# comparator_mezzanine.net
KiCad netlist of a schematic drawn in Altium Designer
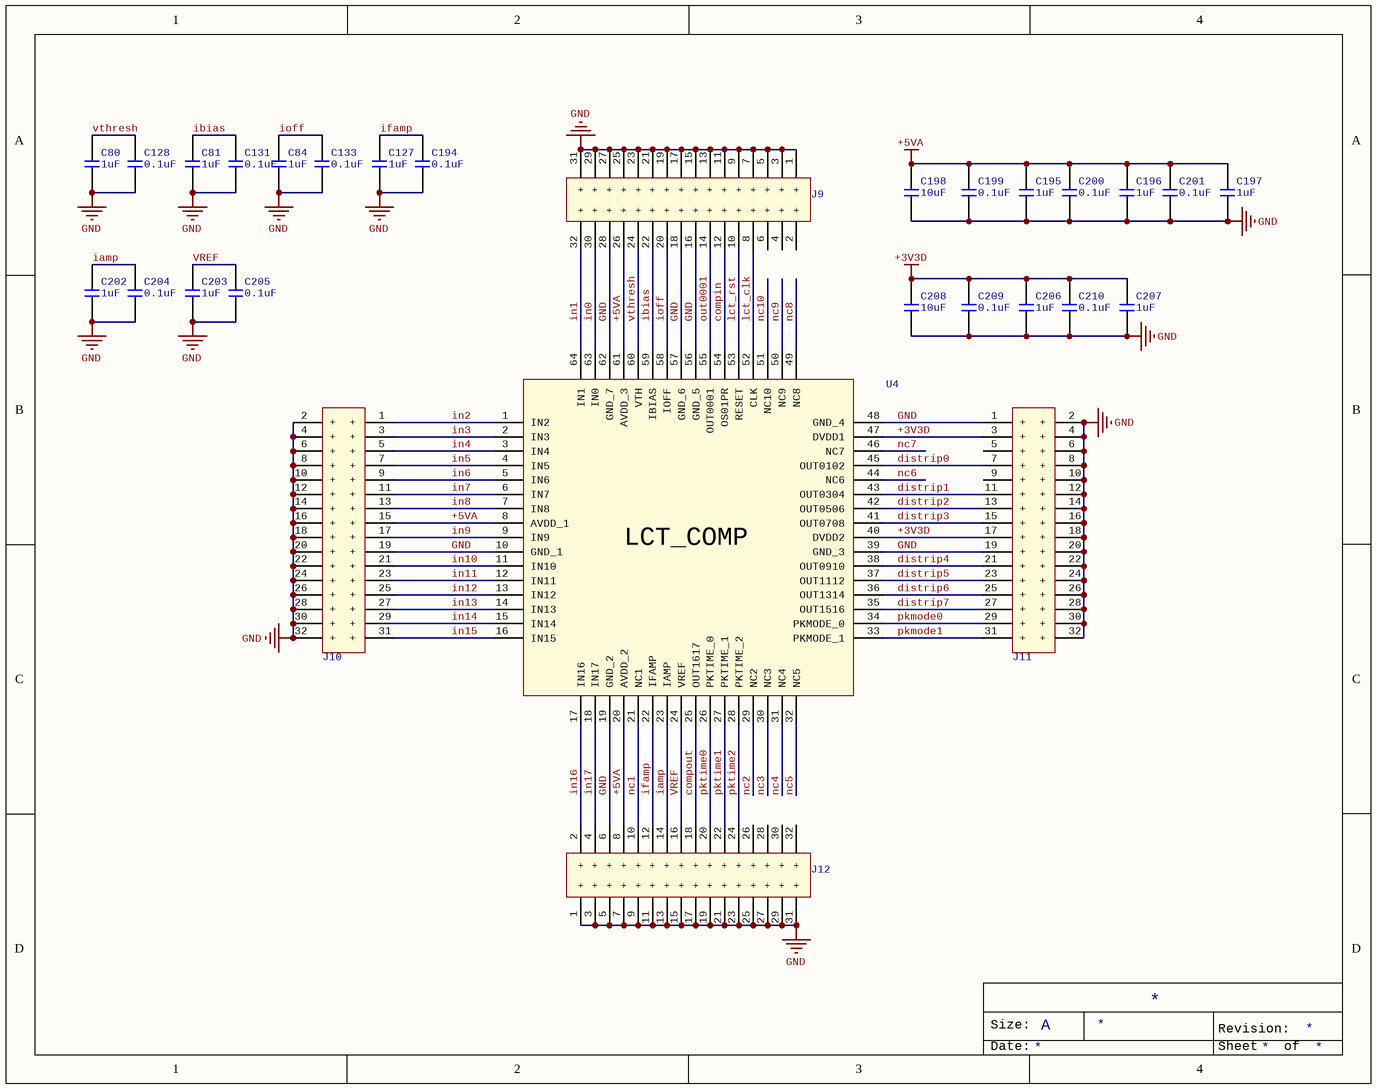
[diagram p0: comparator_mezzanine.SchDoc]

(export (version "E")
  (design (tool "Eeschema 10.0.6"))
  (components
    (comp (ref "C80")
      (value "1uF")
      (footprint "C0603")
      (description "CAP2, CER, 1.0uF, 10%, 25V, 0603")
      (libsource (lib "stdlib") (part "Murata/GRM188R61E105KA12D"))
    )
    (comp (ref "C81")
      (value "1uF")
      (footprint "C0603")
      (description "CAP2, CER, 1.0uF, 10%, 25V, 0603")
      (libsource (lib "stdlib") (part "Murata/GRM188R61E105KA12D"))
    )
    (comp (ref "C84")
      (value "1uF")
      (footprint "C0603")
      (description "CAP2, CER, 1.0uF, 10%, 25V, 0603")
      (libsource (lib "stdlib") (part "Murata/GRM188R61E105KA12D"))
    )
    (comp (ref "C127")
      (value "1uF")
      (footprint "C0603")
      (description "CAP2, CER, 1.0uF, 10%, 25V, 0603")
      (libsource (lib "stdlib") (part "Murata/GRM188R61E105KA12D"))
    )
    (comp (ref "C128")
      (value "0.1uF")
      (footprint "C0603")
      (description "CAP-CER, 2, 0.1uF, 10%, 50V, 0603, X7R")
      (fields
        (field (name "MANUFACTURER") "AVX Corporation")
        (field (name "MANUFACTURER PART NUMBER") "06035C104KAT2A")
      )
      (libsource (lib "stdlib") (part "CAP/06035C104KAT2A"))
    )
    (comp (ref "C131")
      (value "0.1uF")
      (footprint "C0603")
      (description "CAP-CER, 2, 0.1uF, 10%, 50V, 0603, X7R")
      (fields
        (field (name "MANUFACTURER") "AVX Corporation")
        (field (name "MANUFACTURER PART NUMBER") "06035C104KAT2A")
      )
      (libsource (lib "stdlib") (part "CAP/06035C104KAT2A"))
    )
    (comp (ref "C133")
      (value "0.1uF")
      (footprint "C0603")
      (description "CAP-CER, 2, 0.1uF, 10%, 50V, 0603, X7R")
      (fields
        (field (name "MANUFACTURER") "AVX Corporation")
        (field (name "MANUFACTURER PART NUMBER") "06035C104KAT2A")
      )
      (libsource (lib "stdlib") (part "CAP/06035C104KAT2A"))
    )
    (comp (ref "C194")
      (value "0.1uF")
      (footprint "C0603")
      (description "CAP-CER, 2, 0.1uF, 10%, 50V, 0603, X7R")
      (fields
        (field (name "MANUFACTURER") "AVX Corporation")
        (field (name "MANUFACTURER PART NUMBER") "06035C104KAT2A")
      )
      (libsource (lib "stdlib") (part "CAP/06035C104KAT2A"))
    )
    (comp (ref "C195")
      (value "1uF")
      (footprint "C0603")
      (description "CAP2, CER, 1.0uF, 10%, 25V, 0603")
      (libsource (lib "stdlib") (part "Murata/GRM188R61E105KA12D"))
    )
    (comp (ref "C196")
      (value "1uF")
      (footprint "C0603")
      (description "CAP2, CER, 1.0uF, 10%, 25V, 0603")
      (libsource (lib "stdlib") (part "Murata/GRM188R61E105KA12D"))
    )
    (comp (ref "C197")
      (value "1uF")
      (footprint "C0603")
      (description "CAP2, CER, 1.0uF, 10%, 25V, 0603")
      (libsource (lib "stdlib") (part "Murata/GRM188R61E105KA12D"))
    )
    (comp (ref "C198")
      (value "10uF")
      (footprint "c1206")
      (description "CAP-CER, 2, 10uF, 10%, 35V, 1206")
      (fields
        (field (name "MANUFACTURER") "Taiyo Yuden")
        (field (name "MANUFACTURER PART NUMBER") "GMK316F106ZL-T")
      )
      (libsource (lib "stdlib") (part "CAP/GMK316F106ZL-T"))
    )
    (comp (ref "C199")
      (value "0.1uF")
      (footprint "C0603")
      (description "CAP-CER, 2, 0.1uF, 10%, 50V, 0603, X7R")
      (fields
        (field (name "MANUFACTURER") "AVX Corporation")
        (field (name "MANUFACTURER PART NUMBER") "06035C104KAT2A")
      )
      (libsource (lib "stdlib") (part "CAP/06035C104KAT2A"))
    )
    (comp (ref "C200")
      (value "0.1uF")
      (footprint "C0603")
      (description "CAP-CER, 2, 0.1uF, 10%, 50V, 0603, X7R")
      (fields
        (field (name "MANUFACTURER") "AVX Corporation")
        (field (name "MANUFACTURER PART NUMBER") "06035C104KAT2A")
      )
      (libsource (lib "stdlib") (part "CAP/06035C104KAT2A"))
    )
    (comp (ref "C201")
      (value "0.1uF")
      (footprint "C0603")
      (description "CAP-CER, 2, 0.1uF, 10%, 50V, 0603, X7R")
      (fields
        (field (name "MANUFACTURER") "AVX Corporation")
        (field (name "MANUFACTURER PART NUMBER") "06035C104KAT2A")
      )
      (libsource (lib "stdlib") (part "CAP/06035C104KAT2A"))
    )
    (comp (ref "C202")
      (value "1uF")
      (footprint "C0603")
      (description "CAP2, CER, 1.0uF, 10%, 25V, 0603")
      (libsource (lib "stdlib") (part "Murata/GRM188R61E105KA12D"))
    )
    (comp (ref "C203")
      (value "1uF")
      (footprint "C0603")
      (description "CAP2, CER, 1.0uF, 10%, 25V, 0603")
      (libsource (lib "stdlib") (part "Murata/GRM188R61E105KA12D"))
    )
    (comp (ref "C204")
      (value "0.1uF")
      (footprint "C0603")
      (description "CAP-CER, 2, 0.1uF, 10%, 50V, 0603, X7R")
      (fields
        (field (name "MANUFACTURER") "AVX Corporation")
        (field (name "MANUFACTURER PART NUMBER") "06035C104KAT2A")
      )
      (libsource (lib "stdlib") (part "CAP/06035C104KAT2A"))
    )
    (comp (ref "C205")
      (value "0.1uF")
      (footprint "C0603")
      (description "CAP-CER, 2, 0.1uF, 10%, 50V, 0603, X7R")
      (fields
        (field (name "MANUFACTURER") "AVX Corporation")
        (field (name "MANUFACTURER PART NUMBER") "06035C104KAT2A")
      )
      (libsource (lib "stdlib") (part "CAP/06035C104KAT2A"))
    )
    (comp (ref "C206")
      (value "1uF")
      (footprint "C0603")
      (description "CAP2, CER, 1.0uF, 10%, 25V, 0603")
      (libsource (lib "stdlib") (part "Murata/GRM188R61E105KA12D"))
    )
    (comp (ref "C207")
      (value "1uF")
      (footprint "C0603")
      (description "CAP2, CER, 1.0uF, 10%, 25V, 0603")
      (libsource (lib "stdlib") (part "Murata/GRM188R61E105KA12D"))
    )
    (comp (ref "C208")
      (value "10uF")
      (footprint "c1206")
      (description "CAP-CER, 2, 10uF, 10%, 35V, 1206")
      (fields
        (field (name "MANUFACTURER") "Taiyo Yuden")
        (field (name "MANUFACTURER PART NUMBER") "GMK316F106ZL-T")
      )
      (libsource (lib "stdlib") (part "CAP/GMK316F106ZL-T"))
    )
    (comp (ref "C209")
      (value "0.1uF")
      (footprint "C0603")
      (description "CAP-CER, 2, 0.1uF, 10%, 50V, 0603, X7R")
      (fields
        (field (name "MANUFACTURER") "AVX Corporation")
        (field (name "MANUFACTURER PART NUMBER") "06035C104KAT2A")
      )
      (libsource (lib "stdlib") (part "CAP/06035C104KAT2A"))
    )
    (comp (ref "C210")
      (value "0.1uF")
      (footprint "C0603")
      (description "CAP-CER, 2, 0.1uF, 10%, 50V, 0603, X7R")
      (fields
        (field (name "MANUFACTURER") "AVX Corporation")
        (field (name "MANUFACTURER PART NUMBER") "06035C104KAT2A")
      )
      (libsource (lib "stdlib") (part "CAP/06035C104KAT2A"))
    )
    (comp (ref "J9")
      (value "HEADER 16x02")
      (footprint "HEADER 16X02")
      (libsource (lib "stdlib") (part "HEADER 16x02"))
    )
    (comp (ref "J10")
      (value "HEADER 16x02")
      (footprint "HEADER 16X02")
      (libsource (lib "stdlib") (part "HEADER 16x02"))
    )
    (comp (ref "J11")
      (value "HEADER 16x02")
      (footprint "HEADER 16X02")
      (libsource (lib "") (part "HEADER 16x02_1"))
    )
    (comp (ref "J12")
      (value "HEADER 16x02")
      (footprint "HEADER 16X02")
      (libsource (lib "") (part "HEADER 16x02_2"))
    )
    (comp (ref "U4")
      (value "UCLA/LCT_COMP")
      (footprint "FPQ-64-0.8-10")
      (description "UCLA LCT Comparator")
      (libsource (lib "stdlib") (part "UCLA/LCT_COMP"))
    )
  )
  (nets
    (net (code "1") (name "+3V3D") (class "Default")
      (node (ref "C206") (pin "2") (pinfunction "2_2") (pintype "passive"))
      (node (ref "C207") (pin "2") (pinfunction "2_2") (pintype "passive"))
      (node (ref "C208") (pin "1") (pinfunction "5_1") (pintype "passive"))
      (node (ref "C209") (pin "2") (pinfunction "2_2") (pintype "passive"))
      (node (ref "C210") (pin "2") (pinfunction "2_2") (pintype "passive"))
      (node (ref "J11") (pin "17") (pinfunction "+_17") (pintype "passive"))
      (node (ref "J11") (pin "3") (pinfunction "+_3") (pintype "passive"))
      (node (ref "U4") (pin "40") (pinfunction "DVDD2_40") (pintype "passive"))
      (node (ref "U4") (pin "47") (pinfunction "DVDD1_47") (pintype "passive"))
    )
    (net (code "2") (name "+5VA") (class "Default")
      (node (ref "C195") (pin "2") (pinfunction "2_2") (pintype "passive"))
      (node (ref "C196") (pin "2") (pinfunction "2_2") (pintype "passive"))
      (node (ref "C197") (pin "2") (pinfunction "2_2") (pintype "passive"))
      (node (ref "C198") (pin "1") (pinfunction "5_1") (pintype "passive"))
      (node (ref "C199") (pin "2") (pinfunction "2_2") (pintype "passive"))
      (node (ref "C200") (pin "2") (pinfunction "2_2") (pintype "passive"))
      (node (ref "C201") (pin "2") (pinfunction "2_2") (pintype "passive"))
      (node (ref "J10") (pin "15") (pinfunction "+_15") (pintype "passive"))
      (node (ref "J12") (pin "8") (pinfunction "+_8") (pintype "passive"))
      (node (ref "J9") (pin "26") (pinfunction "+_26") (pintype "passive"))
      (node (ref "U4") (pin "20") (pinfunction "AVDD_2_20") (pintype "passive"))
      (node (ref "U4") (pin "61") (pinfunction "AVDD_3_61") (pintype "passive"))
      (node (ref "U4") (pin "8") (pinfunction "AVDD_1_8") (pintype "passive"))
    )
    (net (code "3") (name "/VREF") (class "Default")
      (node (ref "C203") (pin "2") (pinfunction "2_2") (pintype "passive"))
      (node (ref "C205") (pin "2") (pinfunction "2_2") (pintype "passive"))
      (node (ref "J12") (pin "16") (pinfunction "+_16") (pintype "passive"))
      (node (ref "U4") (pin "24") (pinfunction "VREF_24") (pintype "passive"))
    )
    (net (code "4") (name "/compin") (class "Default")
      (node (ref "J9") (pin "12") (pinfunction "+_12") (pintype "passive"))
      (node (ref "U4") (pin "54") (pinfunction "OS01PR_54") (pintype "passive"))
    )
    (net (code "5") (name "/compout") (class "Default")
      (node (ref "J12") (pin "18") (pinfunction "+_18") (pintype "passive"))
      (node (ref "U4") (pin "25") (pinfunction "OUT1617_25") (pintype "passive"))
    )
    (net (code "6") (name "/distrip0") (class "Default")
      (node (ref "J11") (pin "7") (pinfunction "+_7") (pintype "passive"))
      (node (ref "U4") (pin "45") (pinfunction "OUT0102_45") (pintype "passive"))
    )
    (net (code "7") (name "/distrip1") (class "Default")
      (node (ref "J11") (pin "11") (pinfunction "+_11") (pintype "passive"))
      (node (ref "U4") (pin "43") (pinfunction "OUT0304_43") (pintype "passive"))
    )
    (net (code "8") (name "/distrip2") (class "Default")
      (node (ref "J11") (pin "13") (pinfunction "+_13") (pintype "passive"))
      (node (ref "U4") (pin "42") (pinfunction "OUT0506_42") (pintype "passive"))
    )
    (net (code "9") (name "/distrip3") (class "Default")
      (node (ref "J11") (pin "15") (pinfunction "+_15") (pintype "passive"))
      (node (ref "U4") (pin "41") (pinfunction "OUT0708_41") (pintype "passive"))
    )
    (net (code "10") (name "/distrip4") (class "Default")
      (node (ref "J11") (pin "21") (pinfunction "+_21") (pintype "passive"))
      (node (ref "U4") (pin "38") (pinfunction "OUT0910_38") (pintype "passive"))
    )
    (net (code "11") (name "/distrip5") (class "Default")
      (node (ref "J11") (pin "23") (pinfunction "+_23") (pintype "passive"))
      (node (ref "U4") (pin "37") (pinfunction "OUT1112_37") (pintype "passive"))
    )
    (net (code "12") (name "/distrip6") (class "Default")
      (node (ref "J11") (pin "25") (pinfunction "+_25") (pintype "passive"))
      (node (ref "U4") (pin "36") (pinfunction "OUT1314_36") (pintype "passive"))
    )
    (net (code "13") (name "/distrip7") (class "Default")
      (node (ref "J11") (pin "27") (pinfunction "+_27") (pintype "passive"))
      (node (ref "U4") (pin "35") (pinfunction "OUT1516_35") (pintype "passive"))
    )
    (net (code "14") (name "/iamp") (class "Default")
      (node (ref "C202") (pin "2") (pinfunction "2_2") (pintype "passive"))
      (node (ref "C204") (pin "2") (pinfunction "2_2") (pintype "passive"))
      (node (ref "J12") (pin "14") (pinfunction "+_14") (pintype "passive"))
      (node (ref "U4") (pin "23") (pinfunction "IAMP_23") (pintype "passive"))
    )
    (net (code "15") (name "/ibias") (class "Default")
      (node (ref "C131") (pin "2") (pinfunction "2_2") (pintype "passive"))
      (node (ref "C81") (pin "2") (pinfunction "2_2") (pintype "passive"))
      (node (ref "J9") (pin "22") (pinfunction "+_22") (pintype "passive"))
      (node (ref "U4") (pin "59") (pinfunction "IBIAS_59") (pintype "passive"))
    )
    (net (code "16") (name "/ifamp") (class "Default")
      (node (ref "C127") (pin "2") (pinfunction "2_2") (pintype "passive"))
      (node (ref "C194") (pin "2") (pinfunction "2_2") (pintype "passive"))
      (node (ref "J12") (pin "12") (pinfunction "+_12") (pintype "passive"))
      (node (ref "U4") (pin "22") (pinfunction "IFAMP_22") (pintype "passive"))
    )
    (net (code "17") (name "/in0") (class "Default")
      (node (ref "J9") (pin "30") (pinfunction "+_30") (pintype "passive"))
      (node (ref "U4") (pin "63") (pinfunction "IN0_63") (pintype "passive"))
    )
    (net (code "18") (name "/in1") (class "Default")
      (node (ref "J9") (pin "32") (pinfunction "+_32") (pintype "passive"))
      (node (ref "U4") (pin "64") (pinfunction "IN1_64") (pintype "passive"))
    )
    (net (code "19") (name "/in2") (class "Default")
      (node (ref "J10") (pin "1") (pinfunction "+_1") (pintype "passive"))
      (node (ref "U4") (pin "1") (pinfunction "IN2_1") (pintype "passive"))
    )
    (net (code "20") (name "/in3") (class "Default")
      (node (ref "J10") (pin "3") (pinfunction "+_3") (pintype "passive"))
      (node (ref "U4") (pin "2") (pinfunction "IN3_2") (pintype "passive"))
    )
    (net (code "21") (name "/in4") (class "Default")
      (node (ref "J10") (pin "5") (pinfunction "+_5") (pintype "passive"))
      (node (ref "U4") (pin "3") (pinfunction "IN4_3") (pintype "passive"))
    )
    (net (code "22") (name "/in5") (class "Default")
      (node (ref "J10") (pin "7") (pinfunction "+_7") (pintype "passive"))
      (node (ref "U4") (pin "4") (pinfunction "IN5_4") (pintype "passive"))
    )
    (net (code "23") (name "/in6") (class "Default")
      (node (ref "J10") (pin "9") (pinfunction "+_9") (pintype "passive"))
      (node (ref "U4") (pin "5") (pinfunction "IN6_5") (pintype "passive"))
    )
    (net (code "24") (name "/in7") (class "Default")
      (node (ref "J10") (pin "11") (pinfunction "+_11") (pintype "passive"))
      (node (ref "U4") (pin "6") (pinfunction "IN7_6") (pintype "passive"))
    )
    (net (code "25") (name "/in8") (class "Default")
      (node (ref "J10") (pin "13") (pinfunction "+_13") (pintype "passive"))
      (node (ref "U4") (pin "7") (pinfunction "IN8_7") (pintype "passive"))
    )
    (net (code "26") (name "/in9") (class "Default")
      (node (ref "J10") (pin "17") (pinfunction "+_17") (pintype "passive"))
      (node (ref "U4") (pin "9") (pinfunction "IN9_9") (pintype "passive"))
    )
    (net (code "27") (name "/in10") (class "Default")
      (node (ref "J10") (pin "21") (pinfunction "+_21") (pintype "passive"))
      (node (ref "U4") (pin "11") (pinfunction "IN10_11") (pintype "passive"))
    )
    (net (code "28") (name "/in11") (class "Default")
      (node (ref "J10") (pin "23") (pinfunction "+_23") (pintype "passive"))
      (node (ref "U4") (pin "12") (pinfunction "IN11_12") (pintype "passive"))
    )
    (net (code "29") (name "/in12") (class "Default")
      (node (ref "J10") (pin "25") (pinfunction "+_25") (pintype "passive"))
      (node (ref "U4") (pin "13") (pinfunction "IN12_13") (pintype "passive"))
    )
    (net (code "30") (name "/in13") (class "Default")
      (node (ref "J10") (pin "27") (pinfunction "+_27") (pintype "passive"))
      (node (ref "U4") (pin "14") (pinfunction "IN13_14") (pintype "passive"))
    )
    (net (code "31") (name "/in14") (class "Default")
      (node (ref "J10") (pin "29") (pinfunction "+_29") (pintype "passive"))
      (node (ref "U4") (pin "15") (pinfunction "IN14_15") (pintype "passive"))
    )
    (net (code "32") (name "/in15") (class "Default")
      (node (ref "J10") (pin "31") (pinfunction "+_31") (pintype "passive"))
      (node (ref "U4") (pin "16") (pinfunction "IN15_16") (pintype "passive"))
    )
    (net (code "33") (name "/in16") (class "Default")
      (node (ref "J12") (pin "2") (pinfunction "+_2") (pintype "passive"))
      (node (ref "U4") (pin "17") (pinfunction "IN16_17") (pintype "passive"))
    )
    (net (code "34") (name "/in17") (class "Default")
      (node (ref "J12") (pin "4") (pinfunction "+_4") (pintype "passive"))
      (node (ref "U4") (pin "18") (pinfunction "IN17_18") (pintype "passive"))
    )
    (net (code "35") (name "/ioff") (class "Default")
      (node (ref "C133") (pin "2") (pinfunction "2_2") (pintype "passive"))
      (node (ref "C84") (pin "2") (pinfunction "2_2") (pintype "passive"))
      (node (ref "J9") (pin "20") (pinfunction "+_20") (pintype "passive"))
      (node (ref "U4") (pin "58") (pinfunction "IOFF_58") (pintype "passive"))
    )
    (net (code "36") (name "/lct_clk") (class "Default")
      (node (ref "J9") (pin "8") (pinfunction "+_8") (pintype "passive"))
      (node (ref "U4") (pin "52") (pinfunction "CLK_52") (pintype "passive"))
    )
    (net (code "37") (name "/lct_rst") (class "Default")
      (node (ref "J9") (pin "10") (pinfunction "+_10") (pintype "passive"))
      (node (ref "U4") (pin "53") (pinfunction "RESET_53") (pintype "passive"))
    )
    (net (code "38") (name "/nc1") (class "Default")
      (node (ref "J12") (pin "10") (pinfunction "+_10") (pintype "passive"))
      (node (ref "U4") (pin "21") (pinfunction "NC1_21") (pintype "passive"))
    )
    (net (code "39") (name "/nc2") (class "Default")
      (node (ref "U4") (pin "29") (pinfunction "NC2_29") (pintype "passive"))
    )
    (net (code "40") (name "/nc3") (class "Default")
      (node (ref "U4") (pin "30") (pinfunction "NC3_30") (pintype "passive"))
    )
    (net (code "41") (name "/nc4") (class "Default")
      (node (ref "U4") (pin "31") (pinfunction "NC4_31") (pintype "passive"))
    )
    (net (code "42") (name "/nc5") (class "Default")
      (node (ref "U4") (pin "32") (pinfunction "NC5_32") (pintype "passive"))
    )
    (net (code "43") (name "/nc6") (class "Default")
      (node (ref "U4") (pin "44") (pinfunction "NC6_44") (pintype "passive"))
    )
    (net (code "44") (name "/nc7") (class "Default")
      (node (ref "U4") (pin "46") (pinfunction "NC7_46") (pintype "passive"))
    )
    (net (code "45") (name "/nc8") (class "Default")
      (node (ref "U4") (pin "49") (pinfunction "NC8_49") (pintype "passive"))
    )
    (net (code "46") (name "/nc9") (class "Default")
      (node (ref "U4") (pin "50") (pinfunction "NC9_50") (pintype "passive"))
    )
    (net (code "47") (name "/nc10") (class "Default")
      (node (ref "U4") (pin "51") (pinfunction "NC10_51") (pintype "passive"))
    )
    (net (code "48") (name "/out0001") (class "Default")
      (node (ref "J9") (pin "14") (pinfunction "+_14") (pintype "passive"))
      (node (ref "U4") (pin "55") (pinfunction "OUT0001_55") (pintype "passive"))
    )
    (net (code "49") (name "/pkmode0") (class "Default")
      (node (ref "J11") (pin "29") (pinfunction "+_29") (pintype "passive"))
      (node (ref "U4") (pin "34") (pinfunction "PKMODE_0_34") (pintype "passive"))
    )
    (net (code "50") (name "/pkmode1") (class "Default")
      (node (ref "J11") (pin "31") (pinfunction "+_31") (pintype "passive"))
      (node (ref "U4") (pin "33") (pinfunction "PKMODE_1_33") (pintype "passive"))
    )
    (net (code "51") (name "/pktime0") (class "Default")
      (node (ref "J12") (pin "20") (pinfunction "+_20") (pintype "passive"))
      (node (ref "U4") (pin "26") (pinfunction "PKTIME_0_26") (pintype "passive"))
    )
    (net (code "52") (name "/pktime1") (class "Default")
      (node (ref "J12") (pin "22") (pinfunction "+_22") (pintype "passive"))
      (node (ref "U4") (pin "27") (pinfunction "PKTIME_1_27") (pintype "passive"))
    )
    (net (code "53") (name "/pktime2") (class "Default")
      (node (ref "J12") (pin "24") (pinfunction "+_24") (pintype "passive"))
      (node (ref "U4") (pin "28") (pinfunction "PKTIME_2_28") (pintype "passive"))
    )
    (net (code "54") (name "/vthresh") (class "Default")
      (node (ref "C128") (pin "2") (pinfunction "2_2") (pintype "passive"))
      (node (ref "C80") (pin "2") (pinfunction "2_2") (pintype "passive"))
      (node (ref "J9") (pin "24") (pinfunction "+_24") (pintype "passive"))
      (node (ref "U4") (pin "60") (pinfunction "VTH_60") (pintype "passive"))
    )
    (net (code "55") (name "GND") (class "Default")
      (node (ref "C127") (pin "1") (pinfunction "5_1") (pintype "passive"))
      (node (ref "C128") (pin "1") (pinfunction "5_1") (pintype "passive"))
      (node (ref "C131") (pin "1") (pinfunction "5_1") (pintype "passive"))
      (node (ref "C133") (pin "1") (pinfunction "5_1") (pintype "passive"))
      (node (ref "C194") (pin "1") (pinfunction "5_1") (pintype "passive"))
      (node (ref "C195") (pin "1") (pinfunction "5_1") (pintype "passive"))
      (node (ref "C196") (pin "1") (pinfunction "5_1") (pintype "passive"))
      (node (ref "C197") (pin "1") (pinfunction "5_1") (pintype "passive"))
      (node (ref "C198") (pin "2") (pinfunction "2_2") (pintype "passive"))
      (node (ref "C199") (pin "1") (pinfunction "5_1") (pintype "passive"))
      (node (ref "C200") (pin "1") (pinfunction "5_1") (pintype "passive"))
      (node (ref "C201") (pin "1") (pinfunction "5_1") (pintype "passive"))
      (node (ref "C202") (pin "1") (pinfunction "5_1") (pintype "passive"))
      (node (ref "C203") (pin "1") (pinfunction "5_1") (pintype "passive"))
      (node (ref "C204") (pin "1") (pinfunction "5_1") (pintype "passive"))
      (node (ref "C205") (pin "1") (pinfunction "5_1") (pintype "passive"))
      (node (ref "C206") (pin "1") (pinfunction "5_1") (pintype "passive"))
      (node (ref "C207") (pin "1") (pinfunction "5_1") (pintype "passive"))
      (node (ref "C208") (pin "2") (pinfunction "2_2") (pintype "passive"))
      (node (ref "C209") (pin "1") (pinfunction "5_1") (pintype "passive"))
      (node (ref "C210") (pin "1") (pinfunction "5_1") (pintype "passive"))
      (node (ref "C80") (pin "1") (pinfunction "5_1") (pintype "passive"))
      (node (ref "C81") (pin "1") (pinfunction "5_1") (pintype "passive"))
      (node (ref "C84") (pin "1") (pinfunction "5_1") (pintype "passive"))
      (node (ref "J10") (pin "10") (pinfunction "+_10") (pintype "passive"))
      (node (ref "J10") (pin "12") (pinfunction "+_12") (pintype "passive"))
      (node (ref "J10") (pin "14") (pinfunction "+_14") (pintype "passive"))
      (node (ref "J10") (pin "16") (pinfunction "+_16") (pintype "passive"))
      (node (ref "J10") (pin "18") (pinfunction "+_18") (pintype "passive"))
      (node (ref "J10") (pin "19") (pinfunction "+_19") (pintype "passive"))
      (node (ref "J10") (pin "2") (pinfunction "+_2") (pintype "passive"))
      (node (ref "J10") (pin "20") (pinfunction "+_20") (pintype "passive"))
      (node (ref "J10") (pin "22") (pinfunction "+_22") (pintype "passive"))
      (node (ref "J10") (pin "24") (pinfunction "+_24") (pintype "passive"))
      (node (ref "J10") (pin "26") (pinfunction "+_26") (pintype "passive"))
      (node (ref "J10") (pin "28") (pinfunction "+_28") (pintype "passive"))
      (node (ref "J10") (pin "30") (pinfunction "+_30") (pintype "passive"))
      (node (ref "J10") (pin "32") (pinfunction "+_32") (pintype "passive"))
      (node (ref "J10") (pin "4") (pinfunction "+_4") (pintype "passive"))
      (node (ref "J10") (pin "6") (pinfunction "+_6") (pintype "passive"))
      (node (ref "J10") (pin "8") (pinfunction "+_8") (pintype "passive"))
      (node (ref "J11") (pin "1") (pinfunction "+_1") (pintype "passive"))
      (node (ref "J11") (pin "10") (pinfunction "+_10") (pintype "passive"))
      (node (ref "J11") (pin "12") (pinfunction "+_12") (pintype "passive"))
      (node (ref "J11") (pin "14") (pinfunction "+_14") (pintype "passive"))
      (node (ref "J11") (pin "16") (pinfunction "+_16") (pintype "passive"))
      (node (ref "J11") (pin "18") (pinfunction "+_18") (pintype "passive"))
      (node (ref "J11") (pin "19") (pinfunction "+_19") (pintype "passive"))
      (node (ref "J11") (pin "2") (pinfunction "+_2") (pintype "passive"))
      (node (ref "J11") (pin "20") (pinfunction "+_20") (pintype "passive"))
      (node (ref "J11") (pin "22") (pinfunction "+_22") (pintype "passive"))
      (node (ref "J11") (pin "24") (pinfunction "+_24") (pintype "passive"))
      (node (ref "J11") (pin "26") (pinfunction "+_26") (pintype "passive"))
      (node (ref "J11") (pin "28") (pinfunction "+_28") (pintype "passive"))
      (node (ref "J11") (pin "30") (pinfunction "+_30") (pintype "passive"))
      (node (ref "J11") (pin "32") (pinfunction "+_32") (pintype "passive"))
      (node (ref "J11") (pin "4") (pinfunction "+_4") (pintype "passive"))
      (node (ref "J11") (pin "6") (pinfunction "+_6") (pintype "passive"))
      (node (ref "J11") (pin "8") (pinfunction "+_8") (pintype "passive"))
      (node (ref "J12") (pin "1") (pinfunction "+_1") (pintype "passive"))
      (node (ref "J12") (pin "11") (pinfunction "+_11") (pintype "passive"))
      (node (ref "J12") (pin "13") (pinfunction "+_13") (pintype "passive"))
      (node (ref "J12") (pin "15") (pinfunction "+_15") (pintype "passive"))
      (node (ref "J12") (pin "17") (pinfunction "+_17") (pintype "passive"))
      (node (ref "J12") (pin "19") (pinfunction "+_19") (pintype "passive"))
      (node (ref "J12") (pin "21") (pinfunction "+_21") (pintype "passive"))
      (node (ref "J12") (pin "23") (pinfunction "+_23") (pintype "passive"))
      (node (ref "J12") (pin "25") (pinfunction "+_25") (pintype "passive"))
      (node (ref "J12") (pin "27") (pinfunction "+_27") (pintype "passive"))
      (node (ref "J12") (pin "29") (pinfunction "+_29") (pintype "passive"))
      (node (ref "J12") (pin "3") (pinfunction "+_3") (pintype "passive"))
      (node (ref "J12") (pin "31") (pinfunction "+_31") (pintype "passive"))
      (node (ref "J12") (pin "5") (pinfunction "+_5") (pintype "passive"))
      (node (ref "J12") (pin "6") (pinfunction "+_6") (pintype "passive"))
      (node (ref "J12") (pin "7") (pinfunction "+_7") (pintype "passive"))
      (node (ref "J12") (pin "9") (pinfunction "+_9") (pintype "passive"))
      (node (ref "J9") (pin "1") (pinfunction "+_1") (pintype "passive"))
      (node (ref "J9") (pin "11") (pinfunction "+_11") (pintype "passive"))
      (node (ref "J9") (pin "13") (pinfunction "+_13") (pintype "passive"))
      (node (ref "J9") (pin "15") (pinfunction "+_15") (pintype "passive"))
      (node (ref "J9") (pin "16") (pinfunction "+_16") (pintype "passive"))
      (node (ref "J9") (pin "17") (pinfunction "+_17") (pintype "passive"))
      (node (ref "J9") (pin "18") (pinfunction "+_18") (pintype "passive"))
      (node (ref "J9") (pin "19") (pinfunction "+_19") (pintype "passive"))
      (node (ref "J9") (pin "21") (pinfunction "+_21") (pintype "passive"))
      (node (ref "J9") (pin "23") (pinfunction "+_23") (pintype "passive"))
      (node (ref "J9") (pin "25") (pinfunction "+_25") (pintype "passive"))
      (node (ref "J9") (pin "27") (pinfunction "+_27") (pintype "passive"))
      (node (ref "J9") (pin "28") (pinfunction "+_28") (pintype "passive"))
      (node (ref "J9") (pin "29") (pinfunction "+_29") (pintype "passive"))
      (node (ref "J9") (pin "3") (pinfunction "+_3") (pintype "passive"))
      (node (ref "J9") (pin "31") (pinfunction "+_31") (pintype "passive"))
      (node (ref "J9") (pin "5") (pinfunction "+_5") (pintype "passive"))
      (node (ref "J9") (pin "7") (pinfunction "+_7") (pintype "passive"))
      (node (ref "J9") (pin "9") (pinfunction "+_9") (pintype "passive"))
      (node (ref "U4") (pin "10") (pinfunction "GND_1_10") (pintype "passive"))
      (node (ref "U4") (pin "19") (pinfunction "GND_2_19") (pintype "passive"))
      (node (ref "U4") (pin "39") (pinfunction "GND_3_39") (pintype "passive"))
      (node (ref "U4") (pin "48") (pinfunction "GND_4_48") (pintype "passive"))
      (node (ref "U4") (pin "56") (pinfunction "GND_5_56") (pintype "passive"))
      (node (ref "U4") (pin "57") (pinfunction "GND_6_57") (pintype "passive"))
      (node (ref "U4") (pin "62") (pinfunction "GND_7_62") (pintype "passive"))
    )
    (net (code "56") (name "unconnected-(J9-+-Pad2)") (class "Default")
      (node (ref "J9") (pin "2") (pinfunction "+_2") (pintype "passive"))
    )
    (net (code "57") (name "unconnected-(J9-+-Pad4)") (class "Default")
      (node (ref "J9") (pin "4") (pinfunction "+_4") (pintype "passive"))
    )
    (net (code "58") (name "unconnected-(J9-+-Pad6)") (class "Default")
      (node (ref "J9") (pin "6") (pinfunction "+_6") (pintype "passive"))
    )
    (net (code "59") (name "unconnected-(J11-+-Pad5)") (class "Default")
      (node (ref "J11") (pin "5") (pinfunction "+_5") (pintype "passive"))
    )
    (net (code "60") (name "unconnected-(J11-+-Pad9)") (class "Default")
      (node (ref "J11") (pin "9") (pinfunction "+_9") (pintype "passive"))
    )
    (net (code "61") (name "unconnected-(J12-+-Pad26)") (class "Default")
      (node (ref "J12") (pin "26") (pinfunction "+_26") (pintype "passive"))
    )
    (net (code "62") (name "unconnected-(J12-+-Pad28)") (class "Default")
      (node (ref "J12") (pin "28") (pinfunction "+_28") (pintype "passive"))
    )
    (net (code "63") (name "unconnected-(J12-+-Pad30)") (class "Default")
      (node (ref "J12") (pin "30") (pinfunction "+_30") (pintype "passive"))
    )
    (net (code "64") (name "unconnected-(J12-+-Pad32)") (class "Default")
      (node (ref "J12") (pin "32") (pinfunction "+_32") (pintype "passive"))
    )
  )
)
